# SenseBox-Shield_v11.net
KiCad netlist of a schematic drawn in EAGLE
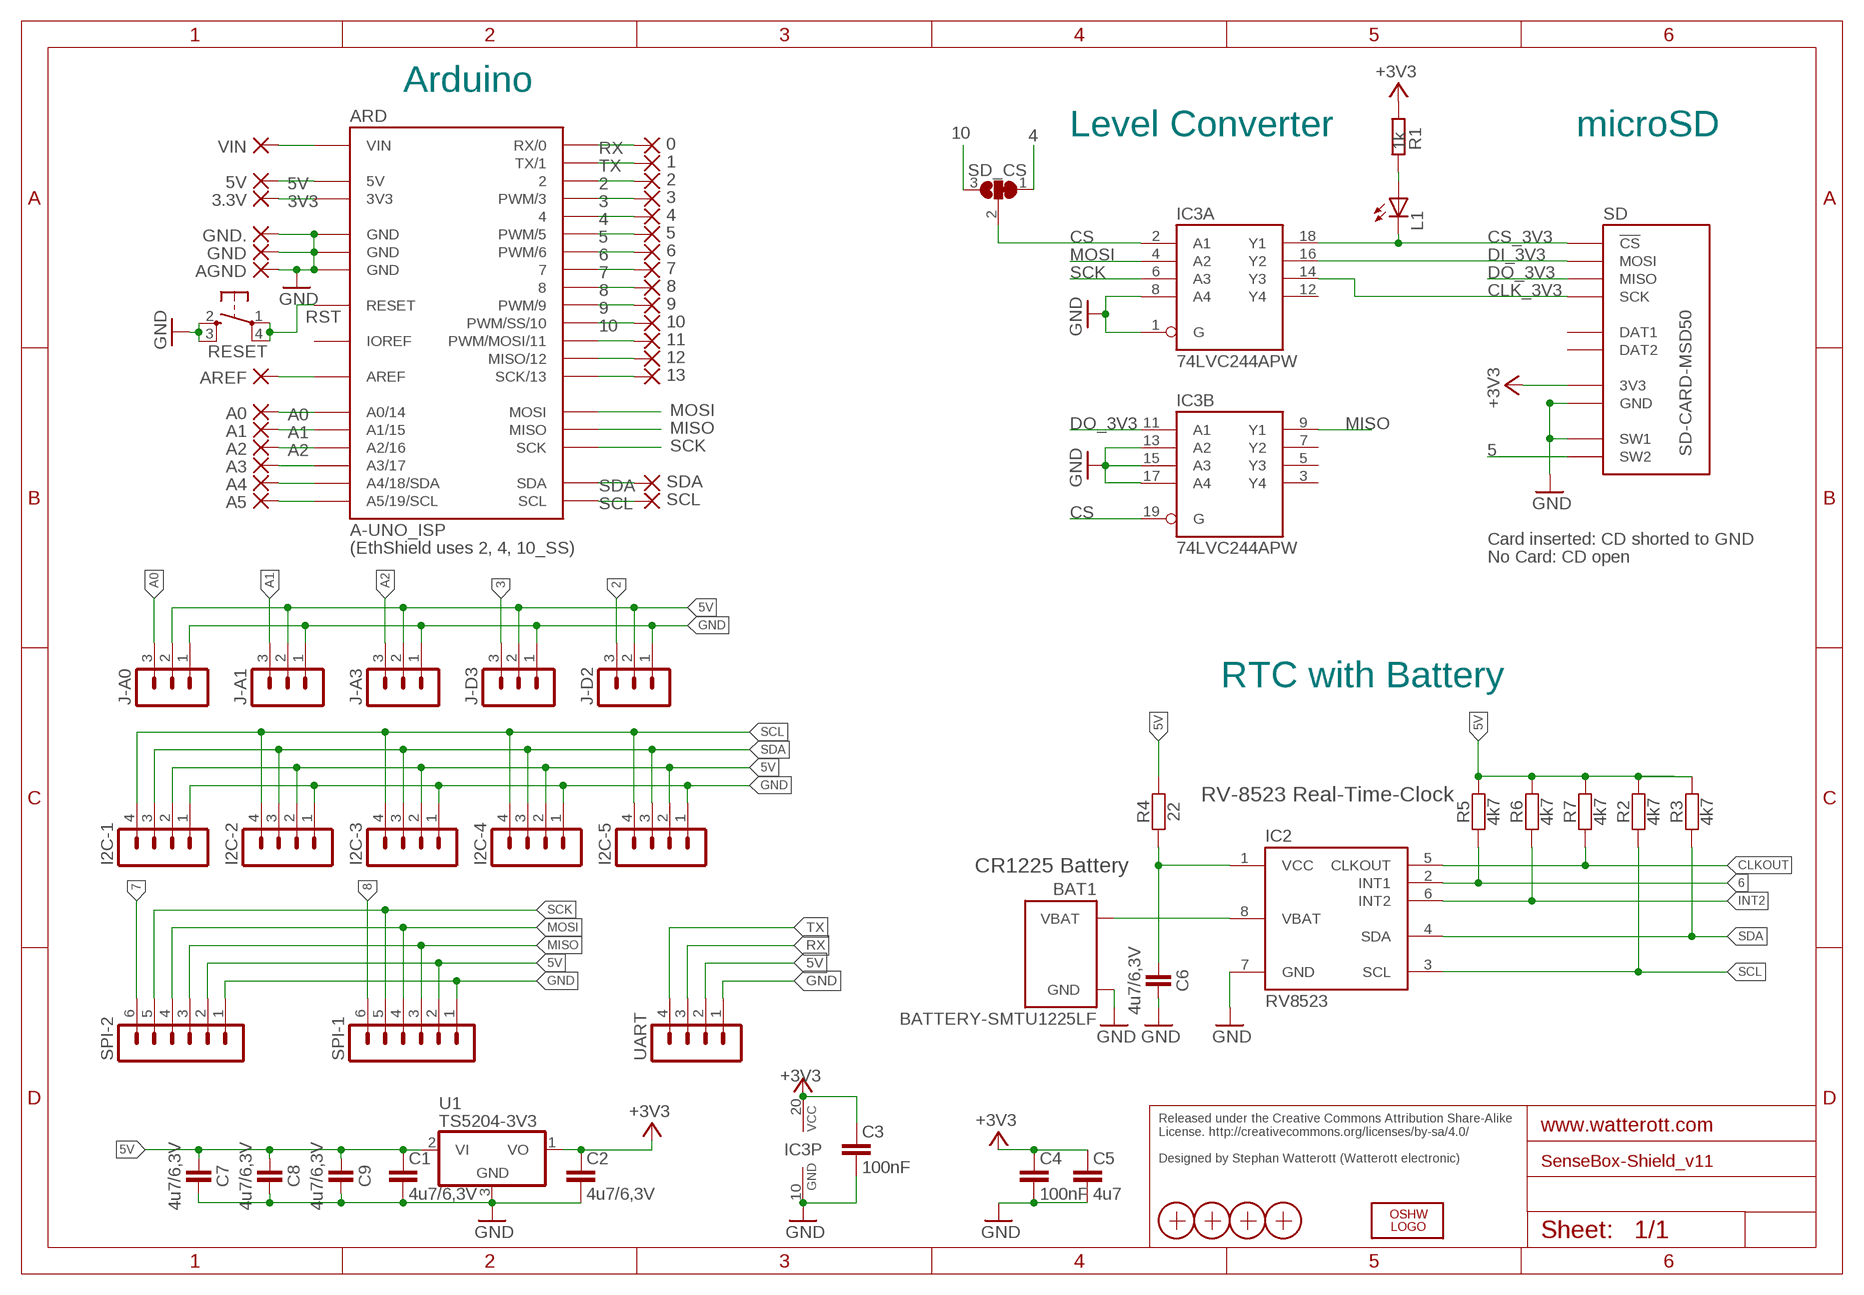
[diagram p0: schematic, sheet 1]

(export (version "E")
  (design (tool "Eeschema 10.0.6"))
  (components
    (comp (ref "0")
      (value "1,6/0,8")
      (footprint "eagle-import:1,6_0,8")
      (libsource (lib "eagle-import") (part "1,6/0,8"))
    )
    (comp (ref "1")
      (value "1,6/0,8")
      (footprint "eagle-import:1,6_0,8")
      (libsource (lib "eagle-import") (part "1,6/0,8"))
    )
    (comp (ref "2")
      (value "1,6/0,8")
      (footprint "eagle-import:1,6_0,8")
      (libsource (lib "eagle-import") (part "1,6/0,8"))
    )
    (comp (ref "3")
      (value "1,6/0,8")
      (footprint "eagle-import:1,6_0,8")
      (libsource (lib "eagle-import") (part "1,6/0,8"))
    )
    (comp (ref "3.3V")
      (value "1,6/0,8")
      (footprint "eagle-import:1,6_0,8")
      (libsource (lib "eagle-import") (part "1,6/0,8"))
    )
    (comp (ref "4")
      (value "1,6/0,8")
      (footprint "eagle-import:1,6_0,8")
      (libsource (lib "eagle-import") (part "1,6/0,8"))
    )
    (comp (ref "5")
      (value "1,6/0,8")
      (footprint "eagle-import:1,6_0,8")
      (libsource (lib "eagle-import") (part "1,6/0,8"))
    )
    (comp (ref "5V")
      (value "1,6/0,8")
      (footprint "eagle-import:1,6_0,8")
      (libsource (lib "eagle-import") (part "1,6/0,8"))
    )
    (comp (ref "6")
      (value "1,6/0,8")
      (footprint "eagle-import:1,6_0,8")
      (libsource (lib "eagle-import") (part "1,6/0,8"))
    )
    (comp (ref "7")
      (value "1,6/0,8")
      (footprint "eagle-import:1,6_0,8")
      (libsource (lib "eagle-import") (part "1,6/0,8"))
    )
    (comp (ref "8")
      (value "1,6/0,8")
      (footprint "eagle-import:1,6_0,8")
      (libsource (lib "eagle-import") (part "1,6/0,8"))
    )
    (comp (ref "9")
      (value "1,6/0,8")
      (footprint "eagle-import:1,6_0,8")
      (libsource (lib "eagle-import") (part "1,6/0,8"))
    )
    (comp (ref "10")
      (value "1,6/0,8")
      (footprint "eagle-import:1,6_0,8")
      (libsource (lib "eagle-import") (part "1,6/0,8"))
    )
    (comp (ref "11")
      (value "1,6/0,8")
      (footprint "eagle-import:1,6_0,8")
      (libsource (lib "eagle-import") (part "1,6/0,8"))
    )
    (comp (ref "12")
      (value "1,6/0,8")
      (footprint "eagle-import:1,6_0,8")
      (libsource (lib "eagle-import") (part "1,6/0,8"))
    )
    (comp (ref "13")
      (value "1,6/0,8")
      (footprint "eagle-import:1,6_0,8")
      (libsource (lib "eagle-import") (part "1,6/0,8"))
    )
    (comp (ref "A0")
      (value "1,6/0,8")
      (footprint "eagle-import:1,6_0,8")
      (libsource (lib "eagle-import") (part "1,6/0,8"))
    )
    (comp (ref "A1")
      (value "1,6/0,8")
      (footprint "eagle-import:1,6_0,8")
      (libsource (lib "eagle-import") (part "1,6/0,8"))
    )
    (comp (ref "A2")
      (value "1,6/0,8")
      (footprint "eagle-import:1,6_0,8")
      (libsource (lib "eagle-import") (part "1,6/0,8"))
    )
    (comp (ref "A3")
      (value "1,6/0,8")
      (footprint "eagle-import:1,6_0,8")
      (libsource (lib "eagle-import") (part "1,6/0,8"))
    )
    (comp (ref "A4")
      (value "1,6/0,8")
      (footprint "eagle-import:1,6_0,8")
      (libsource (lib "eagle-import") (part "1,6/0,8"))
    )
    (comp (ref "A5")
      (value "1,6/0,8")
      (footprint "eagle-import:1,6_0,8")
      (libsource (lib "eagle-import") (part "1,6/0,8"))
    )
    (comp (ref "AGND")
      (value "1,6/0,8")
      (footprint "eagle-import:1,6_0,8")
      (libsource (lib "eagle-import") (part "1,6/0,8"))
    )
    (comp (ref "ARD")
      (value "A-UNO_ISP")
      (footprint "eagle-import:A-UNO-ISP")
      (libsource (lib "eagle-import") (part "A-UNO_ISP"))
    )
    (comp (ref "AREF")
      (value "1,6/0,8")
      (footprint "eagle-import:1,6_0,8")
      (libsource (lib "eagle-import") (part "1,6/0,8"))
    )
    (comp (ref "BAT1")
      (value "BATTERY-SMTU1225LF")
      (footprint "eagle-import:BAT-SMTU1225LF")
      (libsource (lib "eagle-import") (part "BATTERY-SMTU1225LF"))
    )
    (comp (ref "C1")
      (value "4u7/6,3V")
      (footprint "eagle-import:C0402K")
      (libsource (lib "eagle-import") (part "C-EUC0402K"))
    )
    (comp (ref "C2")
      (value "4u7/6,3V")
      (footprint "eagle-import:C0402K")
      (libsource (lib "eagle-import") (part "C-EUC0402K"))
    )
    (comp (ref "C3")
      (value "100nF")
      (footprint "eagle-import:C0402K")
      (libsource (lib "eagle-import") (part "C-EUC0402K"))
    )
    (comp (ref "C4")
      (value "100nF")
      (footprint "eagle-import:C0402K")
      (libsource (lib "eagle-import") (part "C-EUC0402K"))
    )
    (comp (ref "C5")
      (value "4u7")
      (footprint "eagle-import:C0402K")
      (libsource (lib "eagle-import") (part "C-EUC0402K"))
    )
    (comp (ref "C6")
      (value "4u7/6,3V")
      (footprint "eagle-import:C0402")
      (libsource (lib "eagle-import") (part "CAPACITOR-0402"))
    )
    (comp (ref "C7")
      (value "4u7/6,3V")
      (footprint "eagle-import:C0402")
      (libsource (lib "eagle-import") (part "CAPACITOR-0402"))
    )
    (comp (ref "C8")
      (value "4u7/6,3V")
      (footprint "eagle-import:C0402")
      (libsource (lib "eagle-import") (part "CAPACITOR-0402"))
    )
    (comp (ref "C9")
      (value "4u7/6,3V")
      (footprint "eagle-import:C0402")
      (libsource (lib "eagle-import") (part "CAPACITOR-0402"))
    )
    (comp (ref "GND")
      (value "1,6/0,8")
      (footprint "eagle-import:1,6_0,8")
      (libsource (lib "eagle-import") (part "1,6/0,8"))
    )
    (comp (ref "GND.")
      (value "1,6/0,8")
      (footprint "eagle-import:1,6_0,8")
      (libsource (lib "eagle-import") (part "1,6/0,8"))
    )
    (comp (ref "I2C-1")
      (value "JST_PH_4B4B-PH-SM4-TB")
      (footprint "eagle-import:JST_B4B-PH-SM4-TB")
      (libsource (lib "eagle-import") (part "JST_PH_4B4B-PH-SM4-TB"))
    )
    (comp (ref "I2C-2")
      (value "JST_PH_4B4B-PH-SM4-TB")
      (footprint "eagle-import:JST_B4B-PH-SM4-TB")
      (libsource (lib "eagle-import") (part "JST_PH_4B4B-PH-SM4-TB"))
    )
    (comp (ref "I2C-3")
      (value "JST_PH_4B4B-PH-SM4-TB")
      (footprint "eagle-import:JST_B4B-PH-SM4-TB")
      (libsource (lib "eagle-import") (part "JST_PH_4B4B-PH-SM4-TB"))
    )
    (comp (ref "I2C-4")
      (value "JST_PH_4B4B-PH-SM4-TB")
      (footprint "eagle-import:JST_B4B-PH-SM4-TB")
      (libsource (lib "eagle-import") (part "JST_PH_4B4B-PH-SM4-TB"))
    )
    (comp (ref "I2C-5")
      (value "JST_PH_4B4B-PH-SM4-TB")
      (footprint "eagle-import:JST_B4B-PH-SM4-TB")
      (libsource (lib "eagle-import") (part "JST_PH_4B4B-PH-SM4-TB"))
    )
    (comp (ref "IC2")
      (value "RV8523")
      (footprint "eagle-import:RTC-C3")
      (libsource (lib "eagle-import") (part "RV8523-C3"))
    )
    (comp (ref "IC3")
      (value "74LVC244APW")
      (footprint "eagle-import:TSSOP20")
      (libsource (lib "eagle-import") (part "74244PWLVC"))
    )
    (comp (ref "J-A0")
      (value "JST_PH_3B3B-PH-SM4-TB")
      (footprint "eagle-import:JST_B3B-PH-SM4-TB")
      (libsource (lib "eagle-import") (part "JST_PH_3B3B-PH-SM4-TB"))
    )
    (comp (ref "J-A1")
      (value "JST_PH_3B3B-PH-SM4-TB")
      (footprint "eagle-import:JST_B3B-PH-SM4-TB")
      (libsource (lib "eagle-import") (part "JST_PH_3B3B-PH-SM4-TB"))
    )
    (comp (ref "J-A3")
      (value "JST_PH_3B3B-PH-SM4-TB")
      (footprint "eagle-import:JST_B3B-PH-SM4-TB")
      (libsource (lib "eagle-import") (part "JST_PH_3B3B-PH-SM4-TB"))
    )
    (comp (ref "J-D2")
      (value "JST_PH_3B3B-PH-SM4-TB")
      (footprint "eagle-import:JST_B3B-PH-SM4-TB")
      (libsource (lib "eagle-import") (part "JST_PH_3B3B-PH-SM4-TB"))
    )
    (comp (ref "J-D3")
      (value "JST_PH_3B3B-PH-SM4-TB")
      (footprint "eagle-import:JST_B3B-PH-SM4-TB")
      (libsource (lib "eagle-import") (part "JST_PH_3B3B-PH-SM4-TB"))
    )
    (comp (ref "L1")
      (value "LED-0603")
      (footprint "eagle-import:C0603")
      (libsource (lib "eagle-import") (part "LED-0603"))
    )
    (comp (ref "LOGO3")
      (value "OSHW_LOGO_6MILX0100-NT")
      (footprint "eagle-import:OSHW_6X100_NOTEXT")
      (libsource (lib "eagle-import") (part "OSHW_LOGO_6MILX0100-NT"))
    )
    (comp (ref "R1")
      (value "1k")
      (footprint "eagle-import:R0402")
      (libsource (lib "eagle-import") (part "R-EU_R0402"))
    )
    (comp (ref "R2")
      (value "4k7")
      (footprint "eagle-import:C0402")
      (libsource (lib "eagle-import") (part "RESISTOR-0402"))
    )
    (comp (ref "R3")
      (value "4k7")
      (footprint "eagle-import:C0402")
      (libsource (lib "eagle-import") (part "RESISTOR-0402"))
    )
    (comp (ref "R4")
      (value "22")
      (footprint "eagle-import:C0402")
      (libsource (lib "eagle-import") (part "RESISTOR-0402"))
    )
    (comp (ref "R5")
      (value "4k7")
      (footprint "eagle-import:C0402")
      (libsource (lib "eagle-import") (part "RESISTOR-0402"))
    )
    (comp (ref "R6")
      (value "4k7")
      (footprint "eagle-import:C0402")
      (libsource (lib "eagle-import") (part "RESISTOR-0402"))
    )
    (comp (ref "R7")
      (value "4k7")
      (footprint "eagle-import:C0402")
      (libsource (lib "eagle-import") (part "RESISTOR-0402"))
    )
    (comp (ref "RESET")
      (value "SW4S")
      (footprint "eagle-import:SW_SMD4")
      (libsource (lib "eagle-import") (part "SW4S"))
    )
    (comp (ref "SCL")
      (value "1,6/0,8")
      (footprint "eagle-import:1,6_0,8")
      (libsource (lib "eagle-import") (part "1,6/0,8"))
    )
    (comp (ref "SD")
      (value "SD-CARD-MSD50")
      (footprint "eagle-import:SD_5031821853")
      (libsource (lib "eagle-import") (part "SD-CARD-MSD50"))
    )
    (comp (ref "SDA")
      (value "1,6/0,8")
      (footprint "eagle-import:1,6_0,8")
      (libsource (lib "eagle-import") (part "1,6/0,8"))
    )
    (comp (ref "SD_CS")
      (value "SJ2W")
      (footprint "eagle-import:SJ_2")
      (libsource (lib "eagle-import") (part "SJ2W"))
    )
    (comp (ref "SPI-1")
      (value "JST_PH_6B6B-PH-SM4-TB")
      (footprint "eagle-import:JST_B6B-PH-SM4-TB")
      (libsource (lib "eagle-import") (part "JST_PH_6B6B-PH-SM4-TB"))
    )
    (comp (ref "SPI-2")
      (value "JST_PH_6B6B-PH-SM4-TB")
      (footprint "eagle-import:JST_B6B-PH-SM4-TB")
      (libsource (lib "eagle-import") (part "JST_PH_6B6B-PH-SM4-TB"))
    )
    (comp (ref "U1")
      (value "TS5204-3V3")
      (footprint "eagle-import:SOT23")
      (libsource (lib "eagle-import") (part "TS5204"))
    )
    (comp (ref "UART")
      (value "JST_PH_4B4B-PH-SM4-TB")
      (footprint "eagle-import:JST_B4B-PH-SM4-TB")
      (libsource (lib "eagle-import") (part "JST_PH_4B4B-PH-SM4-TB"))
    )
    (comp (ref "VIN")
      (value "1,6/0,8")
      (footprint "eagle-import:1,6_0,8")
      (libsource (lib "eagle-import") (part "1,6/0,8"))
    )
    (comp (ref "X1")
      (value "PASSER")
      (footprint "eagle-import:PASSER")
      (libsource (lib "eagle-import") (part "PASSER"))
    )
    (comp (ref "X2")
      (value "PASSER")
      (footprint "eagle-import:PASSER")
      (libsource (lib "eagle-import") (part "PASSER"))
    )
    (comp (ref "X3")
      (value "PASSER")
      (footprint "eagle-import:PASSER")
      (libsource (lib "eagle-import") (part "PASSER"))
    )
    (comp (ref "X4")
      (value "PASSER")
      (footprint "eagle-import:PASSER")
      (libsource (lib "eagle-import") (part "PASSER"))
    )
  )
  (nets
    (net (code "1") (name "+3V3") (class "Default")
      (node (ref "C2") (pin "1") (pinfunction "1_1") (pintype "passive"))
      (node (ref "C3") (pin "1") (pinfunction "1_1") (pintype "passive"))
      (node (ref "C4") (pin "1") (pinfunction "1_1") (pintype "passive"))
      (node (ref "C5") (pin "1") (pinfunction "1_1") (pintype "passive"))
      (node (ref "IC3") (pin "20") (pinfunction "VCC_20") (pintype "power_in"))
      (node (ref "R1") (pin "1") (pinfunction "1_1") (pintype "passive"))
      (node (ref "SD") (pin "VCC") (pinfunction "3V3_VCC") (pintype "bidirectional"))
      (node (ref "U1") (pin "1") (pinfunction "VO_1") (pintype "passive"))
    )
    (net (code "2") (name "/3V3") (class "Default")
      (node (ref "3.3V") (pin "1") (pinfunction "P_1") (pintype "passive"))
      (node (ref "ARD") (pin "3V3") (pinfunction "3V3_3V3") (pintype "power_in"))
    )
    (net (code "3") (name "/4") (class "Default")
      (node (ref "4") (pin "1") (pinfunction "P_1") (pintype "passive"))
      (node (ref "ARD") (pin "4") (pinfunction "4_4") (pintype "bidirectional"))
      (node (ref "SD_CS") (pin "1") (pinfunction "1_1") (pintype "passive"))
    )
    (net (code "4") (name "/5") (class "Default")
      (node (ref "5") (pin "1") (pinfunction "P_1") (pintype "passive"))
      (node (ref "ARD") (pin "5") (pinfunction "PWM/5_5") (pintype "bidirectional"))
      (node (ref "SD") (pin "SW2") (pinfunction "SW2_SW2") (pintype "bidirectional"))
    )
    (net (code "5") (name "/9") (class "Default")
      (node (ref "9") (pin "1") (pinfunction "P_1") (pintype "passive"))
      (node (ref "ARD") (pin "9") (pinfunction "PWM/9_9") (pintype "bidirectional"))
    )
    (net (code "6") (name "/10") (class "Default")
      (node (ref "10") (pin "1") (pinfunction "P_1") (pintype "passive"))
      (node (ref "ARD") (pin "10") (pinfunction "PWM/SS/10_10") (pintype "bidirectional"))
      (node (ref "SD_CS") (pin "3") (pinfunction "3_3") (pintype "passive"))
    )
    (net (code "7") (name "/CLK_3V3") (class "Default")
      (node (ref "IC3") (pin "14") (pinfunction "Y3_14") (pintype "tri_state"))
      (node (ref "SD") (pin "SCK") (pinfunction "SCK_SCK") (pintype "bidirectional"))
    )
    (net (code "8") (name "/CS") (class "Default")
      (node (ref "IC3") (pin "19") (pinfunction "G_19") (pintype "input"))
      (node (ref "IC3") (pin "2") (pinfunction "A1_2") (pintype "input"))
      (node (ref "SD_CS") (pin "2") (pinfunction "2_2") (pintype "passive"))
    )
    (net (code "9") (name "/CS_3V3") (class "Default")
      (node (ref "IC3") (pin "18") (pinfunction "Y1_18") (pintype "tri_state"))
      (node (ref "L1") (pin "C") (pinfunction "C_C") (pintype "passive"))
      (node (ref "SD") (pin "CS") (pinfunction "~{CS}_CS") (pintype "bidirectional"))
    )
    (net (code "10") (name "/DI_3V3") (class "Default")
      (node (ref "IC3") (pin "16") (pinfunction "Y2_16") (pintype "tri_state"))
      (node (ref "SD") (pin "MOSI") (pinfunction "MOSI_MOSI") (pintype "bidirectional"))
    )
    (net (code "11") (name "/DO_3V3") (class "Default")
      (node (ref "IC3") (pin "11") (pinfunction "A1_11") (pintype "input"))
      (node (ref "SD") (pin "MISO") (pinfunction "MISO_MISO") (pintype "bidirectional"))
    )
    (net (code "12") (name "/IOREF") (class "Default")
      (node (ref "ARD") (pin "IOREF") (pinfunction "IOREF_IOREF") (pintype "power_in"))
    )
    (net (code "13") (name "/RST") (class "Default")
      (node (ref "ARD") (pin "RST@1") (pinfunction "RESET_RST@1") (pintype "bidirectional"))
      (node (ref "RESET") (pin "1") (pinfunction "P_1") (pintype "passive"))
      (node (ref "RESET") (pin "4") (pinfunction "P1_4") (pintype "passive"))
    )
    (net (code "14") (name "2") (class "Default")
      (node (ref "2") (pin "1") (pinfunction "P_1") (pintype "passive"))
      (node (ref "ARD") (pin "2") (pinfunction "2_2") (pintype "bidirectional"))
      (node (ref "J-D2") (pin "3") (pinfunction "3_3") (pintype "passive"))
    )
    (net (code "15") (name "3") (class "Default")
      (node (ref "3") (pin "1") (pinfunction "P_1") (pintype "passive"))
      (node (ref "ARD") (pin "3") (pinfunction "PWM/3_3") (pintype "bidirectional"))
      (node (ref "J-D3") (pin "3") (pinfunction "3_3") (pintype "passive"))
    )
    (net (code "16") (name "5V") (class "Default")
      (node (ref "5V") (pin "1") (pinfunction "P_1") (pintype "passive"))
      (node (ref "ARD") (pin "5V") (pinfunction "5V_5V") (pintype "power_in"))
      (node (ref "C1") (pin "1") (pinfunction "1_1") (pintype "passive"))
      (node (ref "C7") (pin "1") (pinfunction "1_1") (pintype "passive"))
      (node (ref "C8") (pin "1") (pinfunction "1_1") (pintype "passive"))
      (node (ref "C9") (pin "1") (pinfunction "1_1") (pintype "passive"))
      (node (ref "I2C-1") (pin "2") (pinfunction "2_2") (pintype "passive"))
      (node (ref "I2C-2") (pin "2") (pinfunction "2_2") (pintype "passive"))
      (node (ref "I2C-3") (pin "2") (pinfunction "2_2") (pintype "passive"))
      (node (ref "I2C-4") (pin "2") (pinfunction "2_2") (pintype "passive"))
      (node (ref "I2C-5") (pin "2") (pinfunction "2_2") (pintype "passive"))
      (node (ref "J-A0") (pin "2") (pinfunction "2_2") (pintype "passive"))
      (node (ref "J-A1") (pin "2") (pinfunction "2_2") (pintype "passive"))
      (node (ref "J-A3") (pin "2") (pinfunction "2_2") (pintype "passive"))
      (node (ref "J-D2") (pin "2") (pinfunction "2_2") (pintype "passive"))
      (node (ref "J-D3") (pin "2") (pinfunction "2_2") (pintype "passive"))
      (node (ref "R2") (pin "2") (pinfunction "2_2") (pintype "passive"))
      (node (ref "R3") (pin "2") (pinfunction "2_2") (pintype "passive"))
      (node (ref "R4") (pin "2") (pinfunction "2_2") (pintype "passive"))
      (node (ref "R5") (pin "2") (pinfunction "2_2") (pintype "passive"))
      (node (ref "R6") (pin "2") (pinfunction "2_2") (pintype "passive"))
      (node (ref "R7") (pin "2") (pinfunction "2_2") (pintype "passive"))
      (node (ref "SPI-1") (pin "2") (pinfunction "2_2") (pintype "passive"))
      (node (ref "SPI-2") (pin "2") (pinfunction "2_2") (pintype "passive"))
      (node (ref "U1") (pin "2") (pinfunction "VI_2") (pintype "input"))
      (node (ref "UART") (pin "2") (pinfunction "2_2") (pintype "passive"))
    )
    (net (code "17") (name "6") (class "Default")
      (node (ref "6") (pin "1") (pinfunction "P_1") (pintype "passive"))
      (node (ref "ARD") (pin "6") (pinfunction "PWM/6_6") (pintype "bidirectional"))
      (node (ref "IC2") (pin "2") (pinfunction "INT1_2") (pintype "bidirectional"))
      (node (ref "R5") (pin "1") (pinfunction "1_1") (pintype "passive"))
    )
    (net (code "18") (name "7") (class "Default")
      (node (ref "7") (pin "1") (pinfunction "P_1") (pintype "passive"))
      (node (ref "ARD") (pin "7") (pinfunction "7_7") (pintype "bidirectional"))
      (node (ref "SPI-2") (pin "6") (pinfunction "6_6") (pintype "passive"))
    )
    (net (code "19") (name "8") (class "Default")
      (node (ref "8") (pin "1") (pinfunction "P_1") (pintype "passive"))
      (node (ref "ARD") (pin "8") (pinfunction "8_8") (pintype "bidirectional"))
      (node (ref "SPI-1") (pin "6") (pinfunction "6_6") (pintype "passive"))
    )
    (net (code "20") (name "A0") (class "Default")
      (node (ref "A0") (pin "1") (pinfunction "P_1") (pintype "passive"))
      (node (ref "ARD") (pin "A0") (pinfunction "A0/14_A0") (pintype "bidirectional"))
      (node (ref "J-A0") (pin "3") (pinfunction "3_3") (pintype "passive"))
    )
    (net (code "21") (name "A1") (class "Default")
      (node (ref "A1") (pin "1") (pinfunction "P_1") (pintype "passive"))
      (node (ref "ARD") (pin "A1") (pinfunction "A1/15_A1") (pintype "bidirectional"))
      (node (ref "J-A1") (pin "3") (pinfunction "3_3") (pintype "passive"))
    )
    (net (code "22") (name "A2") (class "Default")
      (node (ref "A2") (pin "1") (pinfunction "P_1") (pintype "passive"))
      (node (ref "ARD") (pin "A2") (pinfunction "A2/16_A2") (pintype "bidirectional"))
      (node (ref "J-A3") (pin "3") (pinfunction "3_3") (pintype "passive"))
    )
    (net (code "23") (name "CLKOUT") (class "Default")
      (node (ref "IC2") (pin "5") (pinfunction "CLKOUT_5") (pintype "bidirectional"))
      (node (ref "R7") (pin "1") (pinfunction "1_1") (pintype "passive"))
    )
    (net (code "24") (name "GND") (class "Default")
      (node (ref "AGND") (pin "1") (pinfunction "P_1") (pintype "passive"))
      (node (ref "ARD") (pin "GND@1") (pinfunction "GND_GND@1") (pintype "power_in"))
      (node (ref "ARD") (pin "GND@2") (pinfunction "GND_GND@2") (pintype "power_in"))
      (node (ref "ARD") (pin "GND@3") (pinfunction "GND_GND@3") (pintype "power_in"))
      (node (ref "BAT1") (pin "-") (pinfunction "GND_-") (pintype "power_in"))
      (node (ref "C1") (pin "2") (pinfunction "2_2") (pintype "passive"))
      (node (ref "C2") (pin "2") (pinfunction "2_2") (pintype "passive"))
      (node (ref "C3") (pin "2") (pinfunction "2_2") (pintype "passive"))
      (node (ref "C4") (pin "2") (pinfunction "2_2") (pintype "passive"))
      (node (ref "C5") (pin "2") (pinfunction "2_2") (pintype "passive"))
      (node (ref "C6") (pin "2") (pinfunction "2_2") (pintype "passive"))
      (node (ref "C7") (pin "2") (pinfunction "2_2") (pintype "passive"))
      (node (ref "C8") (pin "2") (pinfunction "2_2") (pintype "passive"))
      (node (ref "C9") (pin "2") (pinfunction "2_2") (pintype "passive"))
      (node (ref "GND") (pin "1") (pinfunction "P_1") (pintype "passive"))
      (node (ref "GND.") (pin "1") (pinfunction "P_1") (pintype "passive"))
      (node (ref "I2C-1") (pin "1") (pinfunction "1_1") (pintype "passive"))
      (node (ref "I2C-2") (pin "1") (pinfunction "1_1") (pintype "passive"))
      (node (ref "I2C-3") (pin "1") (pinfunction "1_1") (pintype "passive"))
      (node (ref "I2C-4") (pin "1") (pinfunction "1_1") (pintype "passive"))
      (node (ref "I2C-5") (pin "1") (pinfunction "1_1") (pintype "passive"))
      (node (ref "IC2") (pin "7") (pinfunction "GND_7") (pintype "power_in"))
      (node (ref "IC3") (pin "1") (pinfunction "G_1") (pintype "input"))
      (node (ref "IC3") (pin "10") (pinfunction "GND_10") (pintype "power_in"))
      (node (ref "IC3") (pin "13") (pinfunction "A2_13") (pintype "input"))
      (node (ref "IC3") (pin "15") (pinfunction "A3_15") (pintype "input"))
      (node (ref "IC3") (pin "17") (pinfunction "A4_17") (pintype "input"))
      (node (ref "IC3") (pin "8") (pinfunction "A4_8") (pintype "input"))
      (node (ref "J-A0") (pin "1") (pinfunction "1_1") (pintype "passive"))
      (node (ref "J-A1") (pin "1") (pinfunction "1_1") (pintype "passive"))
      (node (ref "J-A3") (pin "1") (pinfunction "1_1") (pintype "passive"))
      (node (ref "J-D2") (pin "1") (pinfunction "1_1") (pintype "passive"))
      (node (ref "J-D3") (pin "1") (pinfunction "1_1") (pintype "passive"))
      (node (ref "RESET") (pin "2") (pinfunction "S_2") (pintype "passive"))
      (node (ref "RESET") (pin "3") (pinfunction "S1_3") (pintype "passive"))
      (node (ref "SD") (pin "GND") (pinfunction "GND_GND") (pintype "bidirectional"))
      (node (ref "SD") (pin "SW1") (pinfunction "SW1_SW1") (pintype "bidirectional"))
      (node (ref "SPI-1") (pin "1") (pinfunction "1_1") (pintype "passive"))
      (node (ref "SPI-2") (pin "1") (pinfunction "1_1") (pintype "passive"))
      (node (ref "U1") (pin "3") (pinfunction "GND_3") (pintype "passive"))
      (node (ref "UART") (pin "1") (pinfunction "1_1") (pintype "passive"))
    )
    (net (code "25") (name "INT2") (class "Default")
      (node (ref "IC2") (pin "6") (pinfunction "INT2_6") (pintype "bidirectional"))
      (node (ref "R6") (pin "1") (pinfunction "1_1") (pintype "passive"))
    )
    (net (code "26") (name "MISO") (class "Default")
      (node (ref "ARD") (pin "MISO") (pinfunction "MISO_MISO") (pintype "bidirectional"))
      (node (ref "IC3") (pin "9") (pinfunction "Y1_9") (pintype "tri_state"))
      (node (ref "SPI-1") (pin "3") (pinfunction "3_3") (pintype "passive"))
      (node (ref "SPI-2") (pin "3") (pinfunction "3_3") (pintype "passive"))
    )
    (net (code "27") (name "MOSI") (class "Default")
      (node (ref "ARD") (pin "MOSI") (pinfunction "MOSI_MOSI") (pintype "bidirectional"))
      (node (ref "IC3") (pin "4") (pinfunction "A2_4") (pintype "input"))
      (node (ref "SPI-1") (pin "4") (pinfunction "4_4") (pintype "passive"))
      (node (ref "SPI-2") (pin "4") (pinfunction "4_4") (pintype "passive"))
    )
    (net (code "28") (name "Net-(11-P)") (class "Default")
      (node (ref "11") (pin "1") (pinfunction "P_1") (pintype "passive"))
      (node (ref "ARD") (pin "11") (pinfunction "PWM/MOSI/11_11") (pintype "bidirectional"))
    )
    (net (code "29") (name "Net-(12-P)") (class "Default")
      (node (ref "12") (pin "1") (pinfunction "P_1") (pintype "passive"))
      (node (ref "ARD") (pin "12") (pinfunction "MISO/12_12") (pintype "bidirectional"))
    )
    (net (code "30") (name "Net-(13-P)") (class "Default")
      (node (ref "13") (pin "1") (pinfunction "P_1") (pintype "passive"))
      (node (ref "ARD") (pin "13") (pinfunction "SCK/13_13") (pintype "bidirectional"))
    )
    (net (code "31") (name "Net-(A3-P)") (class "Default")
      (node (ref "A3") (pin "1") (pinfunction "P_1") (pintype "passive"))
      (node (ref "ARD") (pin "A3") (pinfunction "A3/17_A3") (pintype "bidirectional"))
    )
    (net (code "32") (name "Net-(A4-P)") (class "Default")
      (node (ref "A4") (pin "1") (pinfunction "P_1") (pintype "passive"))
      (node (ref "ARD") (pin "A4") (pinfunction "A4/18/SDA_A4") (pintype "bidirectional"))
    )
    (net (code "33") (name "Net-(A5-P)") (class "Default")
      (node (ref "A5") (pin "1") (pinfunction "P_1") (pintype "passive"))
      (node (ref "ARD") (pin "A5") (pinfunction "A5/19/SCL_A5") (pintype "bidirectional"))
    )
    (net (code "34") (name "Net-(AREF-P)") (class "Default")
      (node (ref "ARD") (pin "AREF") (pinfunction "AREF_AREF") (pintype "power_in"))
      (node (ref "AREF") (pin "1") (pinfunction "P_1") (pintype "passive"))
    )
    (net (code "35") (name "Net-(BAT1-VBAT)") (class "Default")
      (node (ref "BAT1") (pin "+") (pinfunction "VBAT_+") (pintype "power_in"))
      (node (ref "IC2") (pin "8") (pinfunction "VBAT_8") (pintype "power_in"))
    )
    (net (code "36") (name "Net-(IC2-VCC)") (class "Default")
      (node (ref "C6") (pin "1") (pinfunction "1_1") (pintype "passive"))
      (node (ref "IC2") (pin "1") (pinfunction "VCC_1") (pintype "power_in"))
      (node (ref "R4") (pin "1") (pinfunction "1_1") (pintype "passive"))
    )
    (net (code "37") (name "Net-(L1-PadA)") (class "Default")
      (node (ref "L1") (pin "A") (pinfunction "A_A") (pintype "passive"))
      (node (ref "R1") (pin "2") (pinfunction "2_2") (pintype "passive"))
    )
    (net (code "38") (name "Net-(VIN-P)") (class "Default")
      (node (ref "ARD") (pin "VIN") (pinfunction "VIN_VIN") (pintype "power_in"))
      (node (ref "VIN") (pin "1") (pinfunction "P_1") (pintype "passive"))
    )
    (net (code "39") (name "RX") (class "Default")
      (node (ref "0") (pin "1") (pinfunction "P_1") (pintype "passive"))
      (node (ref "ARD") (pin "0") (pinfunction "RX/0_0") (pintype "bidirectional"))
      (node (ref "UART") (pin "3") (pinfunction "3_3") (pintype "passive"))
    )
    (net (code "40") (name "SCK") (class "Default")
      (node (ref "ARD") (pin "SCK") (pinfunction "SCK_SCK") (pintype "bidirectional"))
      (node (ref "IC3") (pin "6") (pinfunction "A3_6") (pintype "input"))
      (node (ref "SPI-1") (pin "5") (pinfunction "5_5") (pintype "passive"))
      (node (ref "SPI-2") (pin "5") (pinfunction "5_5") (pintype "passive"))
    )
    (net (code "41") (name "SCL") (class "Default")
      (node (ref "ARD") (pin "SCL") (pinfunction "SCL_SCL") (pintype "bidirectional"))
      (node (ref "I2C-1") (pin "4") (pinfunction "4_4") (pintype "passive"))
      (node (ref "I2C-2") (pin "4") (pinfunction "4_4") (pintype "passive"))
      (node (ref "I2C-3") (pin "4") (pinfunction "4_4") (pintype "passive"))
      (node (ref "I2C-4") (pin "4") (pinfunction "4_4") (pintype "passive"))
      (node (ref "I2C-5") (pin "4") (pinfunction "4_4") (pintype "passive"))
      (node (ref "IC2") (pin "3") (pinfunction "SCL_3") (pintype "bidirectional"))
      (node (ref "R2") (pin "1") (pinfunction "1_1") (pintype "passive"))
      (node (ref "SCL") (pin "1") (pinfunction "P_1") (pintype "passive"))
    )
    (net (code "42") (name "SDA") (class "Default")
      (node (ref "ARD") (pin "SDA") (pinfunction "SDA_SDA") (pintype "bidirectional"))
      (node (ref "I2C-1") (pin "3") (pinfunction "3_3") (pintype "passive"))
      (node (ref "I2C-2") (pin "3") (pinfunction "3_3") (pintype "passive"))
      (node (ref "I2C-3") (pin "3") (pinfunction "3_3") (pintype "passive"))
      (node (ref "I2C-4") (pin "3") (pinfunction "3_3") (pintype "passive"))
      (node (ref "I2C-5") (pin "3") (pinfunction "3_3") (pintype "passive"))
      (node (ref "IC2") (pin "4") (pinfunction "SDA_4") (pintype "bidirectional"))
      (node (ref "R3") (pin "1") (pinfunction "1_1") (pintype "passive"))
      (node (ref "SDA") (pin "1") (pinfunction "P_1") (pintype "passive"))
    )
    (net (code "43") (name "TX") (class "Default")
      (node (ref "1") (pin "1") (pinfunction "P_1") (pintype "passive"))
      (node (ref "ARD") (pin "1") (pinfunction "TX/1_1") (pintype "bidirectional"))
      (node (ref "UART") (pin "4") (pinfunction "4_4") (pintype "passive"))
    )
    (net (code "44") (name "unconnected-(IC3A-Y4-Pad12)") (class "Default")
      (node (ref "IC3") (pin "12") (pinfunction "Y4_12") (pintype "tri_state"))
    )
    (net (code "45") (name "unconnected-(IC3B-Y2-Pad7)") (class "Default")
      (node (ref "IC3") (pin "7") (pinfunction "Y2_7") (pintype "tri_state"))
    )
    (net (code "46") (name "unconnected-(IC3B-Y3-Pad5)") (class "Default")
      (node (ref "IC3") (pin "5") (pinfunction "Y3_5") (pintype "tri_state"))
    )
    (net (code "47") (name "unconnected-(IC3B-Y4-Pad3)") (class "Default")
      (node (ref "IC3") (pin "3") (pinfunction "Y4_3") (pintype "tri_state"))
    )
    (net (code "48") (name "unconnected-(SD-PadDAT1)") (class "Default")
      (node (ref "SD") (pin "DAT1") (pinfunction "DAT1_DAT1") (pintype "bidirectional"))
    )
    (net (code "49") (name "unconnected-(SD-PadDAT2)") (class "Default")
      (node (ref "SD") (pin "DAT2") (pinfunction "DAT2_DAT2") (pintype "bidirectional"))
    )
  )
)
